# MCU.net
KiCad netlist of a schematic drawn in Altium Designer
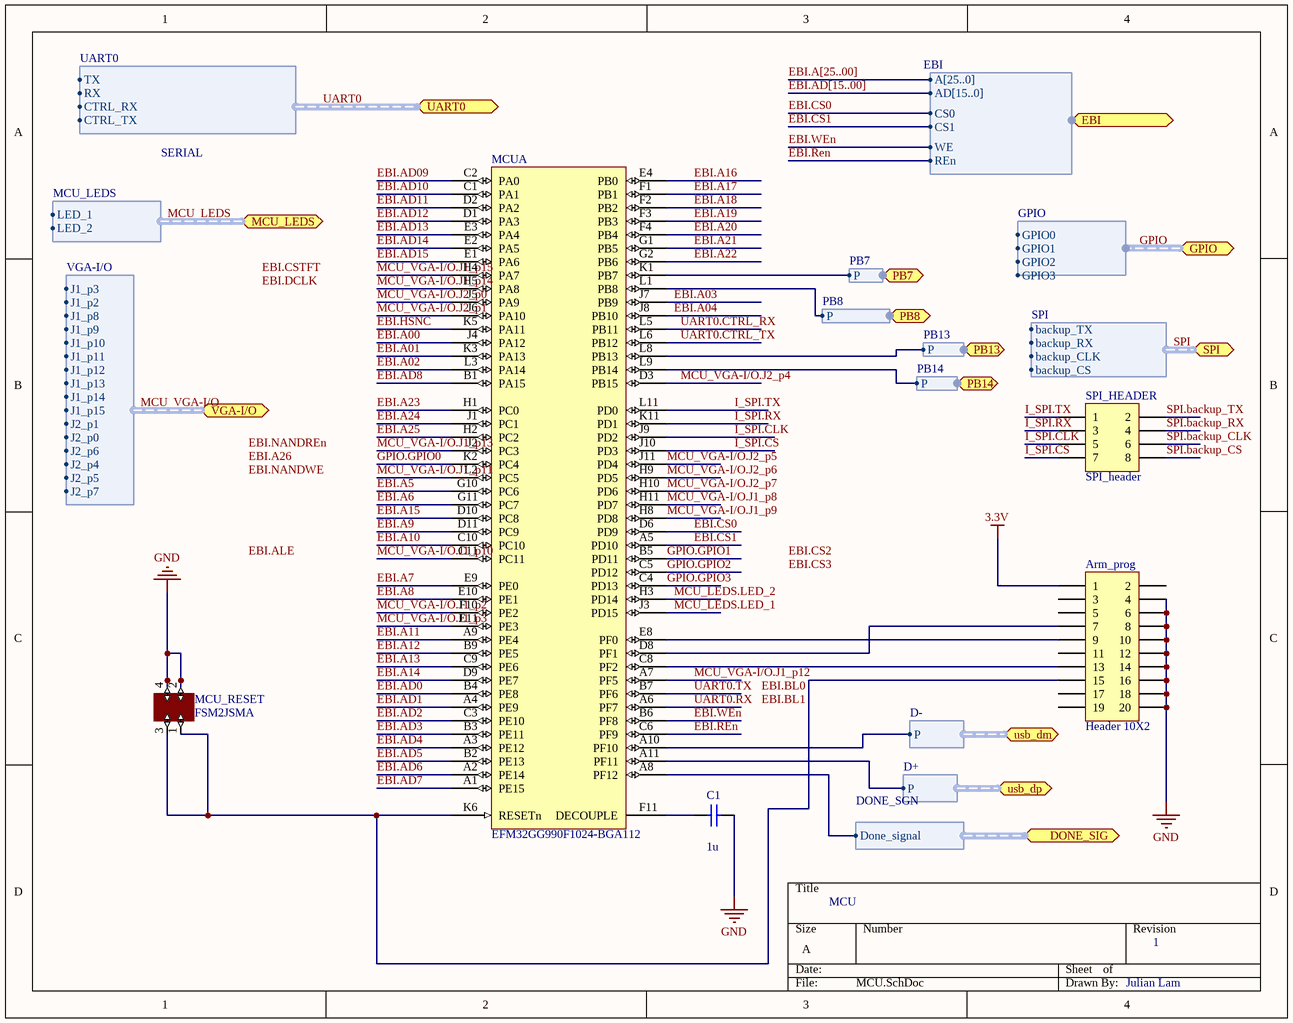
[diagram p0: MCU.SchDoc]

(export (version "E")
  (design (tool "Eeschema 10.0.6"))
  (components
    (comp (ref "Arm_prog")
      (value "Header 10X2")
      (footprint "HDR2X10")
      (description "Header, 10-Pin, Dual row")
      (fields (field (name "PUBLISHER") "Altium Limited"))
      (libsource (lib "Miscellaneous Connectors") (part "Header 10X2"))
    )
    (comp (ref "C1")
      (value "1u")
      (footprint "C1206")
      (description "Capacitor (Semiconductor SIM Model)")
      (fields (field (name "PUBLISHER") "Altium Limited"))
      (libsource (lib "Miscellaneous Devices") (part "Cap Semi"))
    )
    (comp (ref "MCU")
      (value "EFM32GG990F1024-BGA112")
      (footprint "ENMR-BGA112")
      (fields (field (name "GENERIC PART NUMBER") "EFM32GG990"))
      (libsource (lib "Altium Content Vault") (part "CMP-0270-00024-1"))
    )
    (comp (ref "MCU_RESET")
      (value "FSM2JSMA")
      (footprint "button:Button")
      (description "Reset button")
      (libsource (lib "button") (part "switch-button"))
    )
    (comp (ref "SPI_HEADER")
      (value "SPI_header")
      (footprint "HDR2X4")
      (description "Header, 4-Pin, Dual row")
      (fields (field (name "PUBLISHER") "Altium Limited"))
      (libsource (lib "Miscellaneous Connectors") (part "Header 4X2"))
    )
  )
  (nets
    (net (code "19") (name "/Done_signal") (class "Default")
      (node (ref "MCU") (pin "A8") (pinfunction "PF12_A8") (pintype "bidirectional"))
    )
    (net (code "20") (name "/EBI.A00") (class "Default")
      (node (ref "MCU") (pin "J4") (pinfunction "PA12_J4") (pintype "bidirectional"))
    )
    (net (code "21") (name "/EBI.A01") (class "Default")
      (node (ref "MCU") (pin "K3") (pinfunction "PA13_K3") (pintype "bidirectional"))
    )
    (net (code "22") (name "/EBI.A02") (class "Default")
      (node (ref "MCU") (pin "L3") (pinfunction "PA14_L3") (pintype "bidirectional"))
    )
    (net (code "23") (name "/EBI.A03") (class "Default")
      (node (ref "MCU") (pin "J7") (pinfunction "PB9_J7") (pintype "bidirectional"))
    )
    (net (code "24") (name "/EBI.A04") (class "Default")
      (node (ref "MCU") (pin "J8") (pinfunction "PB10_J8") (pintype "bidirectional"))
    )
    (net (code "25") (name "/EBI.A5") (class "Default")
      (node (ref "MCU") (pin "G10") (pinfunction "PC6_G10") (pintype "bidirectional"))
    )
    (net (code "26") (name "/EBI.A6") (class "Default")
      (node (ref "MCU") (pin "G11") (pinfunction "PC7_G11") (pintype "bidirectional"))
    )
    (net (code "27") (name "/EBI.A7") (class "Default")
      (node (ref "MCU") (pin "E9") (pinfunction "PE0_E9") (pintype "bidirectional"))
    )
    (net (code "28") (name "/EBI.A8") (class "Default")
      (node (ref "MCU") (pin "E10") (pinfunction "PE1_E10") (pintype "bidirectional"))
    )
    (net (code "29") (name "/EBI.A9") (class "Default")
      (node (ref "MCU") (pin "D11") (pinfunction "PC9_D11") (pintype "bidirectional"))
    )
    (net (code "30") (name "/EBI.A10") (class "Default")
      (node (ref "MCU") (pin "C10") (pinfunction "PC10_C10") (pintype "bidirectional"))
    )
    (net (code "31") (name "/EBI.A11") (class "Default")
      (node (ref "MCU") (pin "A9") (pinfunction "PE4_A9") (pintype "bidirectional"))
    )
    (net (code "32") (name "/EBI.A12") (class "Default")
      (node (ref "MCU") (pin "B9") (pinfunction "PE5_B9") (pintype "bidirectional"))
    )
    (net (code "33") (name "/EBI.A13") (class "Default")
      (node (ref "MCU") (pin "C9") (pinfunction "PE6_C9") (pintype "bidirectional"))
    )
    (net (code "34") (name "/EBI.A14") (class "Default")
      (node (ref "MCU") (pin "D9") (pinfunction "PE7_D9") (pintype "bidirectional"))
    )
    (net (code "35") (name "/EBI.A15") (class "Default")
      (node (ref "MCU") (pin "D10") (pinfunction "PC8_D10") (pintype "bidirectional"))
    )
    (net (code "36") (name "/EBI.A16") (class "Default")
      (node (ref "MCU") (pin "E4") (pinfunction "PB0_E4") (pintype "bidirectional"))
    )
    (net (code "37") (name "/EBI.A17") (class "Default")
      (node (ref "MCU") (pin "F1") (pinfunction "PB1_F1") (pintype "bidirectional"))
    )
    (net (code "38") (name "/EBI.A18") (class "Default")
      (node (ref "MCU") (pin "F2") (pinfunction "PB2_F2") (pintype "bidirectional"))
    )
    (net (code "39") (name "/EBI.A19") (class "Default")
      (node (ref "MCU") (pin "F3") (pinfunction "PB3_F3") (pintype "bidirectional"))
    )
    (net (code "40") (name "/EBI.A20") (class "Default")
      (node (ref "MCU") (pin "F4") (pinfunction "PB4_F4") (pintype "bidirectional"))
    )
    (net (code "41") (name "/EBI.A21") (class "Default")
      (node (ref "MCU") (pin "G1") (pinfunction "PB5_G1") (pintype "bidirectional"))
    )
    (net (code "42") (name "/EBI.A22") (class "Default")
      (node (ref "MCU") (pin "G2") (pinfunction "PB6_G2") (pintype "bidirectional"))
    )
    (net (code "43") (name "/EBI.A23") (class "Default")
      (node (ref "MCU") (pin "H1") (pinfunction "PC0_H1") (pintype "bidirectional"))
    )
    (net (code "44") (name "/EBI.A24") (class "Default")
      (node (ref "MCU") (pin "J1") (pinfunction "PC1_J1") (pintype "bidirectional"))
    )
    (net (code "45") (name "/EBI.A25") (class "Default")
      (node (ref "MCU") (pin "H2") (pinfunction "PC2_H2") (pintype "bidirectional"))
    )
    (net (code "47") (name "/EBI.AD0") (class "Default")
      (node (ref "MCU") (pin "B4") (pinfunction "PE8_B4") (pintype "bidirectional"))
    )
    (net (code "48") (name "/EBI.AD1") (class "Default")
      (node (ref "MCU") (pin "A4") (pinfunction "PE9_A4") (pintype "bidirectional"))
    )
    (net (code "49") (name "/EBI.AD2") (class "Default")
      (node (ref "MCU") (pin "C3") (pinfunction "PE10_C3") (pintype "bidirectional"))
    )
    (net (code "50") (name "/EBI.AD3") (class "Default")
      (node (ref "MCU") (pin "B3") (pinfunction "PE11_B3") (pintype "bidirectional"))
    )
    (net (code "51") (name "/EBI.AD4") (class "Default")
      (node (ref "MCU") (pin "A3") (pinfunction "PE12_A3") (pintype "bidirectional"))
    )
    (net (code "52") (name "/EBI.AD5") (class "Default")
      (node (ref "MCU") (pin "B2") (pinfunction "PE13_B2") (pintype "bidirectional"))
    )
    (net (code "53") (name "/EBI.AD6") (class "Default")
      (node (ref "MCU") (pin "A2") (pinfunction "PE14_A2") (pintype "bidirectional"))
    )
    (net (code "54") (name "/EBI.AD7") (class "Default")
      (node (ref "MCU") (pin "A1") (pinfunction "PE15_A1") (pintype "bidirectional"))
    )
    (net (code "55") (name "/EBI.AD8") (class "Default")
      (node (ref "MCU") (pin "B1") (pinfunction "PA15_B1") (pintype "bidirectional"))
    )
    (net (code "56") (name "/EBI.AD09") (class "Default")
      (node (ref "MCU") (pin "C2") (pinfunction "PA0_C2") (pintype "bidirectional"))
    )
    (net (code "57") (name "/EBI.AD10") (class "Default")
      (node (ref "MCU") (pin "C1") (pinfunction "PA1_C1") (pintype "bidirectional"))
    )
    (net (code "58") (name "/EBI.AD11") (class "Default")
      (node (ref "MCU") (pin "D2") (pinfunction "PA2_D2") (pintype "bidirectional"))
    )
    (net (code "59") (name "/EBI.AD12") (class "Default")
      (node (ref "MCU") (pin "D1") (pinfunction "PA3_D1") (pintype "bidirectional"))
    )
    (net (code "60") (name "/EBI.AD13") (class "Default")
      (node (ref "MCU") (pin "E3") (pinfunction "PA4_E3") (pintype "bidirectional"))
    )
    (net (code "61") (name "/EBI.AD14") (class "Default")
      (node (ref "MCU") (pin "E2") (pinfunction "PA5_E2") (pintype "bidirectional"))
    )
    (net (code "62") (name "/EBI.AD15") (class "Default")
      (node (ref "MCU") (pin "E1") (pinfunction "PA6_E1") (pintype "bidirectional"))
    )
    (net (code "67") (name "/EBI.CS0") (class "Default")
      (node (ref "MCU") (pin "D6") (pinfunction "PD9_D6") (pintype "bidirectional"))
    )
    (net (code "68") (name "/EBI.CS1") (class "Default")
      (node (ref "MCU") (pin "A5") (pinfunction "PD10_A5") (pintype "bidirectional"))
    )
    (net (code "73") (name "/EBI.HSNC") (class "Default")
      (node (ref "MCU") (pin "K5") (pinfunction "PA11_K5") (pintype "bidirectional"))
    )
    (net (code "76") (name "/EBI.REn") (class "Default")
      (node (ref "MCU") (pin "C6") (pinfunction "PF9_C6") (pintype "bidirectional"))
    )
    (net (code "78") (name "/EBI.WEn") (class "Default")
      (node (ref "MCU") (pin "B6") (pinfunction "PF8_B6") (pintype "bidirectional"))
    )
    (net (code "80") (name "/GPIO.GPIO0") (class "Default")
      (node (ref "MCU") (pin "K2") (pinfunction "PC4_K2") (pintype "bidirectional"))
    )
    (net (code "81") (name "/GPIO.GPIO1") (class "Default")
      (node (ref "MCU") (pin "B5") (pinfunction "PD11_B5") (pintype "bidirectional"))
    )
    (net (code "82") (name "/GPIO.GPIO2") (class "Default")
      (node (ref "MCU") (pin "C5") (pinfunction "PD12_C5") (pintype "bidirectional"))
    )
    (net (code "83") (name "/GPIO.GPIO3") (class "Default")
      (node (ref "MCU") (pin "C4") (pinfunction "PD13_C4") (pintype "bidirectional"))
    )
    (net (code "85") (name "/I_SPI.CLK") (class "Default")
      (node (ref "MCU") (pin "J9") (pinfunction "PD2_J9") (pintype "bidirectional"))
      (node (ref "SPI_HEADER") (pin "5") (pinfunction "5_5") (pintype "passive"))
    )
    (net (code "86") (name "/I_SPI.CS") (class "Default")
      (node (ref "MCU") (pin "J10") (pinfunction "PD3_J10") (pintype "bidirectional"))
      (node (ref "SPI_HEADER") (pin "7") (pinfunction "7_7") (pintype "passive"))
    )
    (net (code "87") (name "/I_SPI.RX") (class "Default")
      (node (ref "MCU") (pin "K11") (pinfunction "PD1_K11") (pintype "bidirectional"))
      (node (ref "SPI_HEADER") (pin "3") (pinfunction "3_3") (pintype "passive"))
    )
    (net (code "88") (name "/I_SPI.TX") (class "Default")
      (node (ref "MCU") (pin "L11") (pinfunction "PD0_L11") (pintype "bidirectional"))
      (node (ref "SPI_HEADER") (pin "1") (pinfunction "1_1") (pintype "passive"))
    )
    (net (code "89") (name "/MCU_LEDS.LED_1") (class "Default")
      (node (ref "MCU") (pin "J3") (pinfunction "PD15_J3") (pintype "bidirectional"))
    )
    (net (code "90") (name "/MCU_LEDS.LED_2") (class "Default")
      (node (ref "MCU") (pin "H3") (pinfunction "PD14_H3") (pintype "bidirectional"))
    )
    (net (code "92") (name "/MCU_VGA-I{slash}O.J1_p2") (class "Default")
      (node (ref "MCU") (pin "F10") (pinfunction "PE2_F10") (pintype "bidirectional"))
    )
    (net (code "93") (name "/MCU_VGA-I{slash}O.J1_p3") (class "Default")
      (node (ref "MCU") (pin "E11") (pinfunction "PE3_E11") (pintype "bidirectional"))
    )
    (net (code "94") (name "/MCU_VGA-I{slash}O.J1_p8") (class "Default")
      (node (ref "MCU") (pin "H11") (pinfunction "PD7_H11") (pintype "bidirectional"))
    )
    (net (code "95") (name "/MCU_VGA-I{slash}O.J1_p9") (class "Default")
      (node (ref "MCU") (pin "H8") (pinfunction "PD8_H8") (pintype "bidirectional"))
    )
    (net (code "96") (name "/MCU_VGA-I{slash}O.J1_p10") (class "Default")
      (node (ref "MCU") (pin "C11") (pinfunction "PC11_C11") (pintype "bidirectional"))
    )
    (net (code "97") (name "/MCU_VGA-I{slash}O.J1_p11") (class "Default")
      (node (ref "MCU") (pin "L2") (pinfunction "PC5_L2") (pintype "bidirectional"))
    )
    (net (code "98") (name "/MCU_VGA-I{slash}O.J1_p12") (class "Default")
      (node (ref "MCU") (pin "A7") (pinfunction "PF5_A7") (pintype "bidirectional"))
    )
    (net (code "99") (name "/MCU_VGA-I{slash}O.J1_p13") (class "Default")
      (node (ref "MCU") (pin "J2") (pinfunction "PC3_J2") (pintype "bidirectional"))
    )
    (net (code "100") (name "/MCU_VGA-I{slash}O.J1_p14") (class "Default")
      (node (ref "MCU") (pin "H5") (pinfunction "PA8_H5") (pintype "bidirectional"))
    )
    (net (code "101") (name "/MCU_VGA-I{slash}O.J1_p15") (class "Default")
      (node (ref "MCU") (pin "H4") (pinfunction "PA7_H4") (pintype "bidirectional"))
    )
    (net (code "102") (name "/MCU_VGA-I{slash}O.J2_p0") (class "Default")
      (node (ref "MCU") (pin "J5") (pinfunction "PA9_J5") (pintype "bidirectional"))
    )
    (net (code "103") (name "/MCU_VGA-I{slash}O.J2_p1") (class "Default")
      (node (ref "MCU") (pin "J6") (pinfunction "PA10_J6") (pintype "bidirectional"))
    )
    (net (code "104") (name "/MCU_VGA-I{slash}O.J2_p4") (class "Default")
      (node (ref "MCU") (pin "D3") (pinfunction "PB15_D3") (pintype "bidirectional"))
    )
    (net (code "105") (name "/MCU_VGA-I{slash}O.J2_p5") (class "Default")
      (node (ref "MCU") (pin "J11") (pinfunction "PD4_J11") (pintype "bidirectional"))
    )
    (net (code "106") (name "/MCU_VGA-I{slash}O.J2_p6") (class "Default")
      (node (ref "MCU") (pin "H9") (pinfunction "PD5_H9") (pintype "bidirectional"))
    )
    (net (code "107") (name "/MCU_VGA-I{slash}O.J2_p7") (class "Default")
      (node (ref "MCU") (pin "H10") (pinfunction "PD6_H10") (pintype "bidirectional"))
    )
    (net (code "109") (name "/SPI.backup_CLK") (class "Default")
      (node (ref "SPI_HEADER") (pin "6") (pinfunction "6_6") (pintype "passive"))
    )
    (net (code "110") (name "/SPI.backup_CS") (class "Default")
      (node (ref "SPI_HEADER") (pin "8") (pinfunction "8_8") (pintype "passive"))
    )
    (net (code "111") (name "/SPI.backup_RX") (class "Default")
      (node (ref "SPI_HEADER") (pin "4") (pinfunction "4_4") (pintype "passive"))
    )
    (net (code "112") (name "/SPI.backup_TX") (class "Default")
      (node (ref "SPI_HEADER") (pin "2") (pinfunction "2_2") (pintype "passive"))
    )
    (net (code "114") (name "/UART0.CTRL_RX") (class "Default")
      (node (ref "MCU") (pin "L5") (pinfunction "PB11_L5") (pintype "bidirectional"))
    )
    (net (code "115") (name "/UART0.CTRL_TX") (class "Default")
      (node (ref "MCU") (pin "L6") (pinfunction "PB12_L6") (pintype "bidirectional"))
    )
    (net (code "116") (name "/UART0.RX") (class "Default")
      (node (ref "MCU") (pin "A6") (pinfunction "PF7_A6") (pintype "bidirectional"))
    )
    (net (code "117") (name "/UART0.TX") (class "Default")
      (node (ref "MCU") (pin "B7") (pinfunction "PF6_B7") (pintype "bidirectional"))
    )
    (net (code "127") (name "3.3V") (class "Default")
      (node (ref "Arm_prog") (pin "1") (pinfunction "1_1") (pintype "passive"))
    )
    (net (code "128") (name "GND") (class "Default")
      (node (ref "Arm_prog") (pin "10") (pinfunction "10_10") (pintype "passive"))
      (node (ref "Arm_prog") (pin "12") (pinfunction "12_12") (pintype "passive"))
      (node (ref "Arm_prog") (pin "14") (pinfunction "14_14") (pintype "passive"))
      (node (ref "Arm_prog") (pin "16") (pinfunction "16_16") (pintype "passive"))
      (node (ref "Arm_prog") (pin "18") (pinfunction "18_18") (pintype "passive"))
      (node (ref "Arm_prog") (pin "20") (pinfunction "20_20") (pintype "passive"))
      (node (ref "Arm_prog") (pin "4") (pinfunction "4_4") (pintype "passive"))
      (node (ref "Arm_prog") (pin "6") (pinfunction "6_6") (pintype "passive"))
      (node (ref "Arm_prog") (pin "8") (pinfunction "8_8") (pintype "passive"))
      (node (ref "C1") (pin "2") (pinfunction "2_2") (pintype "passive"))
      (node (ref "MCU_RESET") (pin "2") (pinfunction "2_2") (pintype "bidirectional"))
      (node (ref "MCU_RESET") (pin "4") (pinfunction "4_4") (pintype "bidirectional"))
    )
    (net (code "129") (name "Net-(MCUA-DECOUPLE)") (class "Default")
      (node (ref "C1") (pin "1") (pinfunction "1_1") (pintype "passive"))
      (node (ref "MCU") (pin "F11") (pinfunction "DECOUPLE_F11") (pintype "passive"))
    )
    (net (code "130") (name "Net-(MCUA-PF0)") (class "Default")
      (node (ref "Arm_prog") (pin "9") (pinfunction "9_9") (pintype "passive"))
      (node (ref "MCU") (pin "E8") (pinfunction "PF0_E8") (pintype "bidirectional"))
    )
    (net (code "131") (name "Net-(MCUA-PF1)") (class "Default")
      (node (ref "Arm_prog") (pin "7") (pinfunction "7_7") (pintype "passive"))
      (node (ref "MCU") (pin "D8") (pinfunction "PF1_D8") (pintype "bidirectional"))
    )
    (net (code "132") (name "Net-(MCUA-PF2)") (class "Default")
      (node (ref "Arm_prog") (pin "13") (pinfunction "13_13") (pintype "passive"))
      (node (ref "MCU") (pin "C8") (pinfunction "PF2_C8") (pintype "bidirectional"))
    )
    (net (code "133") (name "Net-(MCUA-RESETn)") (class "Default")
      (node (ref "Arm_prog") (pin "15") (pinfunction "15_15") (pintype "passive"))
      (node (ref "MCU") (pin "K6") (pinfunction "RESETn_K6") (pintype "input"))
      (node (ref "MCU_RESET") (pin "1") (pinfunction "1_1") (pintype "bidirectional"))
      (node (ref "MCU_RESET") (pin "3") (pinfunction "3_3") (pintype "bidirectional"))
    )
    (net (code "134") (name "unconnected-(Arm_prog-Pad2)") (class "Default")
      (node (ref "Arm_prog") (pin "2") (pinfunction "2_2") (pintype "passive"))
    )
    (net (code "135") (name "unconnected-(Arm_prog-Pad3)") (class "Default")
      (node (ref "Arm_prog") (pin "3") (pinfunction "3_3") (pintype "passive"))
    )
    (net (code "136") (name "unconnected-(Arm_prog-Pad5)") (class "Default")
      (node (ref "Arm_prog") (pin "5") (pinfunction "5_5") (pintype "passive"))
    )
    (net (code "137") (name "unconnected-(Arm_prog-Pad11)") (class "Default")
      (node (ref "Arm_prog") (pin "11") (pinfunction "11_11") (pintype "passive"))
    )
    (net (code "138") (name "unconnected-(Arm_prog-Pad17)") (class "Default")
      (node (ref "Arm_prog") (pin "17") (pinfunction "17_17") (pintype "passive"))
    )
    (net (code "139") (name "unconnected-(Arm_prog-Pad19)") (class "Default")
      (node (ref "Arm_prog") (pin "19") (pinfunction "19_19") (pintype "passive"))
    )
    (net (code "140") (name "unconnected-(MCUA-PB7-PadK1)") (class "Default")
      (node (ref "MCU") (pin "K1") (pinfunction "PB7_K1") (pintype "bidirectional"))
    )
    (net (code "141") (name "unconnected-(MCUA-PB8-PadL1)") (class "Default")
      (node (ref "MCU") (pin "L1") (pinfunction "PB8_L1") (pintype "bidirectional"))
    )
    (net (code "142") (name "unconnected-(MCUA-PB13-PadL8)") (class "Default")
      (node (ref "MCU") (pin "L8") (pinfunction "PB13_L8") (pintype "bidirectional"))
    )
    (net (code "143") (name "unconnected-(MCUA-PB14-PadL9)") (class "Default")
      (node (ref "MCU") (pin "L9") (pinfunction "PB14_L9") (pintype "bidirectional"))
    )
    (net (code "144") (name "unconnected-(MCUA-PF10-PadA10)") (class "Default")
      (node (ref "MCU") (pin "A10") (pinfunction "PF10_A10") (pintype "bidirectional"))
    )
    (net (code "145") (name "unconnected-(MCUA-PF11-PadA11)") (class "Default")
      (node (ref "MCU") (pin "A11") (pinfunction "PF11_A11") (pintype "bidirectional"))
    )
  )
)
